# TM1637_Display.net
KiCad netlist of a schematic drawn in Altium Designer
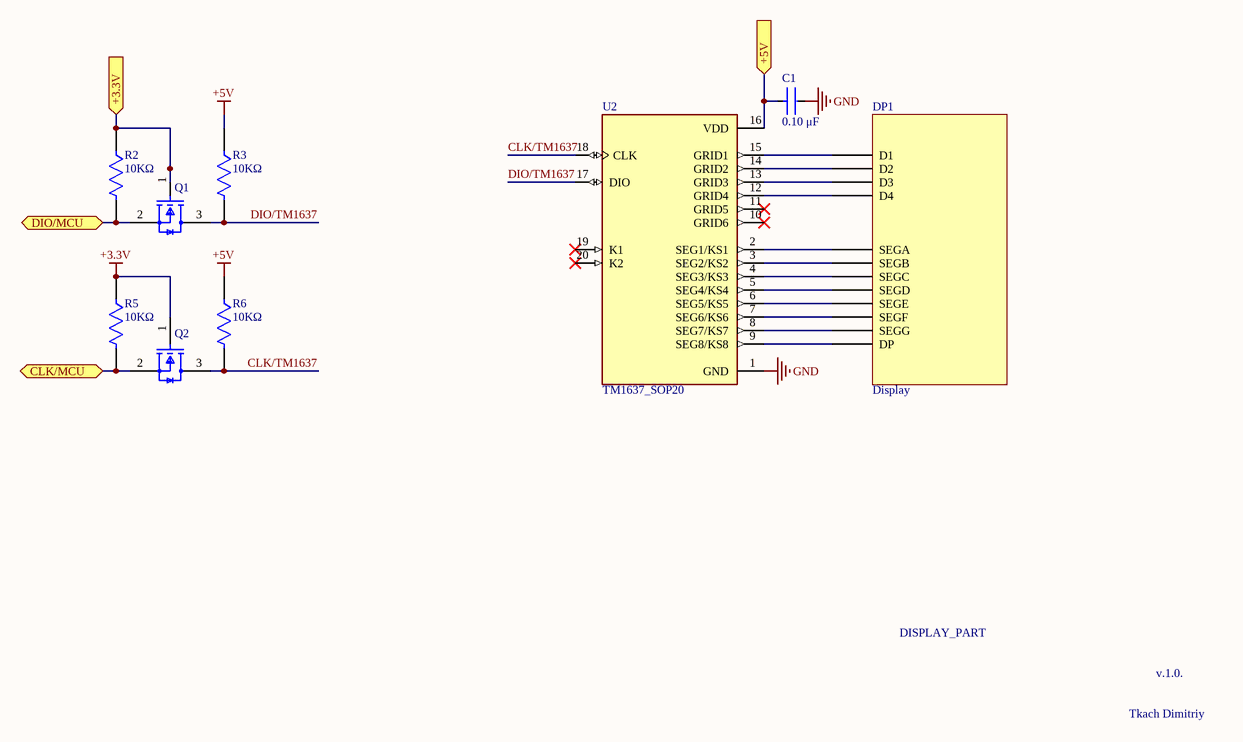
[diagram p0: TM1637_Display.SchDoc]

(export (version "E")
  (design (tool "Eeschema 10.0.6"))
  (components
    (comp (ref "C1")
      (value "C1206C104K5RACAUTO")
      (footprint "CAPC3216X18M")
      (description "CAP CER 0.1UF 50V X7R 1206")
      (fields
        (field (name "MANUFACTURER") "KEMET")
        (field (name "OCTOPART") "https://octopart.com/c1206c104k5racauto-kemet-12595586")
        (field (name "CAPACITANCE") "0.10 μF")
      )
      (libsource (lib "Internal_Lib_Thermostat_STM8") (part "CMP-03020-005759-1"))
    )
    (comp (ref "DP1")
      (value "Display")
      (footprint "3461BS-1")
      (libsource (lib "Internal_Lib_Thermostat_STM8") (part "Component_1_1"))
    )
    (comp (ref "Q1")
      (value "2N7002-7-F")
      (footprint "FP-SOT23-MFG")
      (description "MOSFET N-CH 60V 115MA SOT23-3")
      (fields (field (name "VOLTAGE") "60V"))
      (libsource (lib "Internal_Lib_Thermostat_STM8") (part "3b9c635fedb024a5347a57b145af9cc"))
    )
    (comp (ref "Q2")
      (value "2N7002-7-F")
      (footprint "FP-SOT23-MFG")
      (description "MOSFET N-CH 60V 115MA SOT23-3")
      (fields (field (name "VOLTAGE") "60V"))
      (libsource (lib "Internal_Lib_Thermostat_STM8") (part "3b9c635fedb024a5347a57b145af9cc"))
    )
    (comp (ref "R2")
      (value "CRGP1206F10K")
      (footprint "RESC3216X06M")
      (description "CRGP 1206 10K 1%")
      (fields
        (field (name "OCTOPART") "https://octopart.com/crgp1206f10k-te+connectivity-91018843")
        (field (name "TOLERANCE") "0.01")
        (field (name "RESISTANCE") "10KΩ")
      )
      (libsource (lib "Internal_Lib_Thermostat_STM8") (part "CMP-03211-004788-1"))
    )
    (comp (ref "R3")
      (value "CRGP1206F10K")
      (footprint "RESC3216X06M")
      (description "CRGP 1206 10K 1%")
      (fields
        (field (name "OCTOPART") "https://octopart.com/crgp1206f10k-te+connectivity-91018843")
        (field (name "TOLERANCE") "0.01")
        (field (name "RESISTANCE") "10KΩ")
      )
      (libsource (lib "Internal_Lib_Thermostat_STM8") (part "CMP-03211-004788-1"))
    )
    (comp (ref "R5")
      (value "CRGP1206F10K")
      (footprint "RESC3216X06M")
      (description "CRGP 1206 10K 1%")
      (fields
        (field (name "OCTOPART") "https://octopart.com/crgp1206f10k-te+connectivity-91018843")
        (field (name "TOLERANCE") "0.01")
        (field (name "RESISTANCE") "10KΩ")
      )
      (libsource (lib "Internal_Lib_Thermostat_STM8") (part "CMP-03211-004788-1"))
    )
    (comp (ref "R6")
      (value "CRGP1206F10K")
      (footprint "RESC3216X06M")
      (description "CRGP 1206 10K 1%")
      (fields
        (field (name "OCTOPART") "https://octopart.com/crgp1206f10k-te+connectivity-91018843")
        (field (name "TOLERANCE") "0.01")
        (field (name "RESISTANCE") "10KΩ")
      )
      (libsource (lib "Internal_Lib_Thermostat_STM8") (part "CMP-03211-004788-1"))
    )
    (comp (ref "U2")
      (value "TM1637_SOP20")
      (footprint "SOIC127P1035X255-20N")
      (description "LED Drive Control Special Circuit")
      (fields (field (name "MF") "Titan Micro Electronics"))
      (libsource (lib "Internal_Lib_Thermostat_STM8") (part "TM1637_SOP20"))
    )
  )
  (nets
    (net (code "1") (name "+3.3V") (class "Default")
      (node (ref "Q1") (pin "1") (pinfunction "G_1") (pintype "passive"))
      (node (ref "Q2") (pin "1") (pinfunction "G_1") (pintype "passive"))
      (node (ref "R2") (pin "1") (pinfunction "1_1") (pintype "passive"))
      (node (ref "R5") (pin "1") (pinfunction "1_1") (pintype "passive"))
    )
    (net (code "2") (name "+5V") (class "Default")
      (node (ref "C1") (pin "1") (pinfunction "1_1") (pintype "passive"))
      (node (ref "R3") (pin "1") (pinfunction "1_1") (pintype "passive"))
      (node (ref "R6") (pin "1") (pinfunction "1_1") (pintype "passive"))
      (node (ref "U2") (pin "16") (pinfunction "VDD_16") (pintype "power_in"))
    )
    (net (code "3") (name "/CLK{slash}MCU") (class "Default")
      (node (ref "Q2") (pin "2") (pinfunction "S_2") (pintype "passive"))
      (node (ref "R5") (pin "2") (pinfunction "2_2") (pintype "passive"))
    )
    (net (code "4") (name "/CLK{slash}TM1637") (class "Default")
      (node (ref "Q2") (pin "3") (pinfunction "D_3") (pintype "passive"))
      (node (ref "R6") (pin "2") (pinfunction "2_2") (pintype "passive"))
      (node (ref "U2") (pin "18") (pinfunction "CLK_18") (pintype "bidirectional"))
    )
    (net (code "5") (name "/DIO{slash}MCU") (class "Default")
      (node (ref "Q1") (pin "2") (pinfunction "S_2") (pintype "passive"))
      (node (ref "R2") (pin "2") (pinfunction "2_2") (pintype "passive"))
    )
    (net (code "6") (name "/DIO{slash}TM1637") (class "Default")
      (node (ref "Q1") (pin "3") (pinfunction "D_3") (pintype "passive"))
      (node (ref "R3") (pin "2") (pinfunction "2_2") (pintype "passive"))
      (node (ref "U2") (pin "17") (pinfunction "DIO_17") (pintype "bidirectional"))
    )
    (net (code "7") (name "GND") (class "Default")
      (node (ref "C1") (pin "2") (pinfunction "2_2") (pintype "passive"))
      (node (ref "U2") (pin "1") (pinfunction "GND_1") (pintype "power_in"))
    )
    (net (code "8") (name "Net-(U2-GRID1)") (class "Default")
      (node (ref "DP1") (pin "D1") (pinfunction "D1_D1") (pintype "passive"))
      (node (ref "U2") (pin "15") (pinfunction "GRID1_15") (pintype "output"))
    )
    (net (code "9") (name "Net-(U2-GRID2)") (class "Default")
      (node (ref "DP1") (pin "D2") (pinfunction "D2_D2") (pintype "passive"))
      (node (ref "U2") (pin "14") (pinfunction "GRID2_14") (pintype "output"))
    )
    (net (code "10") (name "Net-(U2-GRID3)") (class "Default")
      (node (ref "DP1") (pin "D3") (pinfunction "D3_D3") (pintype "passive"))
      (node (ref "U2") (pin "13") (pinfunction "GRID3_13") (pintype "output"))
    )
    (net (code "11") (name "Net-(U2-GRID4)") (class "Default")
      (node (ref "DP1") (pin "D4") (pinfunction "D4_D4") (pintype "passive"))
      (node (ref "U2") (pin "12") (pinfunction "GRID4_12") (pintype "output"))
    )
    (net (code "12") (name "Net-(U2-SEG1{slash}KS1)") (class "Default")
      (node (ref "DP1") (pin "SEGA") (pinfunction "SEGA_SEGA") (pintype "passive"))
      (node (ref "U2") (pin "2") (pinfunction "SEG1/KS1_2") (pintype "output"))
    )
    (net (code "13") (name "Net-(U2-SEG2{slash}KS2)") (class "Default")
      (node (ref "DP1") (pin "SEGB") (pinfunction "SEGB_SEGB") (pintype "passive"))
      (node (ref "U2") (pin "3") (pinfunction "SEG2/KS2_3") (pintype "output"))
    )
    (net (code "14") (name "Net-(U2-SEG3{slash}KS3)") (class "Default")
      (node (ref "DP1") (pin "SEGC") (pinfunction "SEGC_SEGC") (pintype "passive"))
      (node (ref "U2") (pin "4") (pinfunction "SEG3/KS3_4") (pintype "output"))
    )
    (net (code "15") (name "Net-(U2-SEG4{slash}KS4)") (class "Default")
      (node (ref "DP1") (pin "SEGD") (pinfunction "SEGD_SEGD") (pintype "passive"))
      (node (ref "U2") (pin "5") (pinfunction "SEG4/KS4_5") (pintype "output"))
    )
    (net (code "16") (name "Net-(U2-SEG5{slash}KS5)") (class "Default")
      (node (ref "DP1") (pin "SEGE") (pinfunction "SEGE_SEGE") (pintype "passive"))
      (node (ref "U2") (pin "6") (pinfunction "SEG5/KS5_6") (pintype "output"))
    )
    (net (code "17") (name "Net-(U2-SEG6{slash}KS6)") (class "Default")
      (node (ref "DP1") (pin "SEGF") (pinfunction "SEGF_SEGF") (pintype "passive"))
      (node (ref "U2") (pin "7") (pinfunction "SEG6/KS6_7") (pintype "output"))
    )
    (net (code "18") (name "Net-(U2-SEG7{slash}KS7)") (class "Default")
      (node (ref "DP1") (pin "SEGG") (pinfunction "SEGG_SEGG") (pintype "passive"))
      (node (ref "U2") (pin "8") (pinfunction "SEG7/KS7_8") (pintype "output"))
    )
    (net (code "19") (name "Net-(U2-SEG8{slash}KS8)") (class "Default")
      (node (ref "DP1") (pin "DP") (pinfunction "DP_DP") (pintype "passive"))
      (node (ref "U2") (pin "9") (pinfunction "SEG8/KS8_9") (pintype "output"))
    )
    (net (code "20") (name "unconnected-(U2-GRID5-Pad11)") (class "Default")
      (node (ref "U2") (pin "11") (pinfunction "GRID5_11") (pintype "output+no_connect"))
    )
    (net (code "21") (name "unconnected-(U2-GRID6-Pad10)") (class "Default")
      (node (ref "U2") (pin "10") (pinfunction "GRID6_10") (pintype "output+no_connect"))
    )
    (net (code "22") (name "unconnected-(U2-K1-Pad19)") (class "Default")
      (node (ref "U2") (pin "19") (pinfunction "K1_19") (pintype "input+no_connect"))
    )
    (net (code "23") (name "unconnected-(U2-K2-Pad20)") (class "Default")
      (node (ref "U2") (pin "20") (pinfunction "K2_20") (pintype "input+no_connect"))
    )
  )
)
